# Joystick_final_rev02.net
KiCad netlist of a schematic drawn in EAGLE
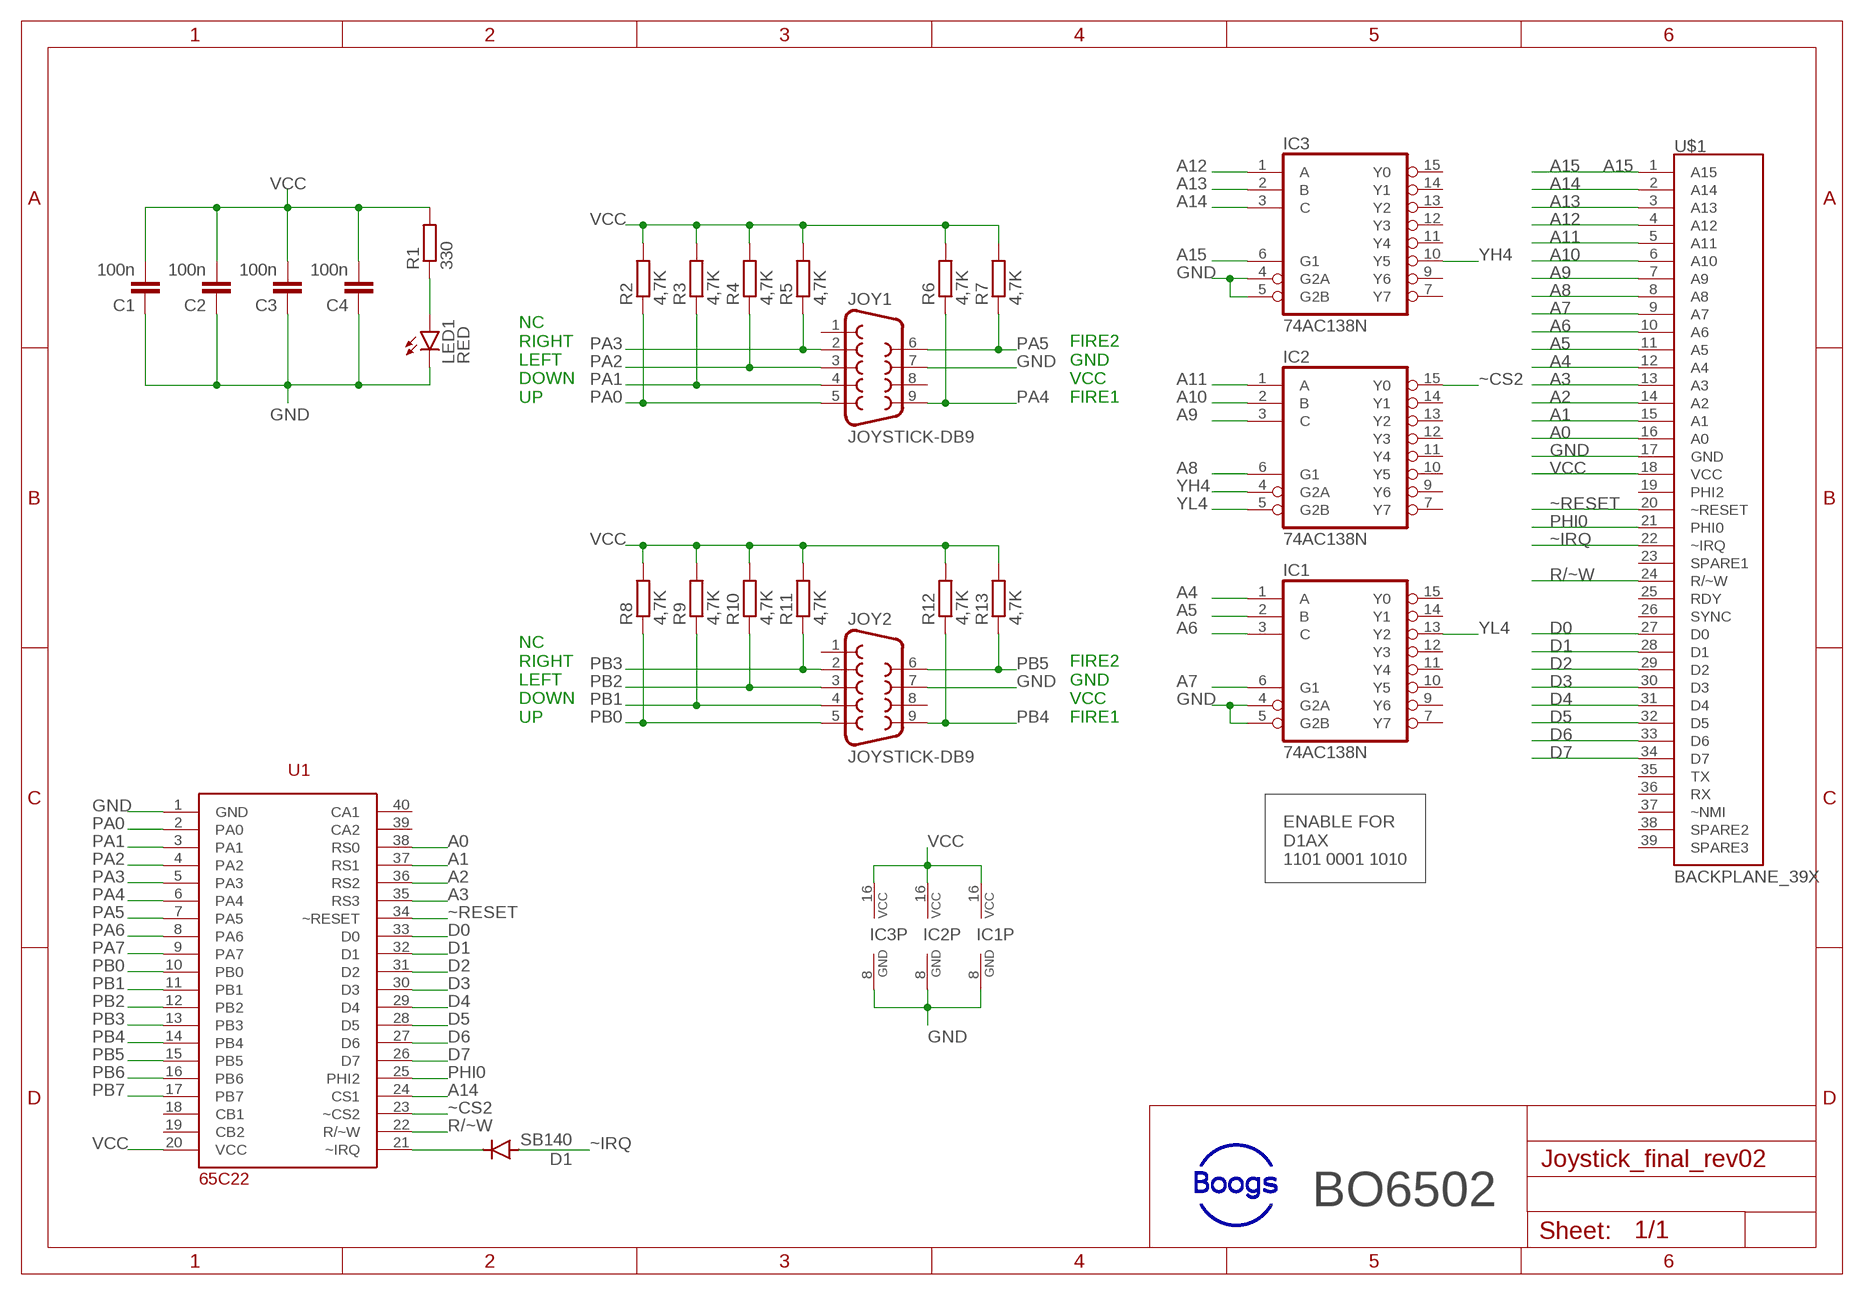
[diagram p0: schematic, sheet 1]

(export (version "E")
  (design (tool "Eeschema 10.0.6"))
  (components
    (comp (ref "C1")
      (value "100n")
      (footprint "eagle-import:C025-025X050")
      (libsource (lib "eagle-import") (part "C-EU025-025X050"))
    )
    (comp (ref "C2")
      (value "100n")
      (footprint "eagle-import:C025-025X050")
      (libsource (lib "eagle-import") (part "C-EU025-025X050"))
    )
    (comp (ref "C3")
      (value "100n")
      (footprint "eagle-import:C025-025X050")
      (libsource (lib "eagle-import") (part "C-EU025-025X050"))
    )
    (comp (ref "C4")
      (value "100n")
      (footprint "eagle-import:C025-025X050")
      (libsource (lib "eagle-import") (part "C-EU025-025X050"))
    )
    (comp (ref "D1")
      (value "SB140")
      (footprint "eagle-import:DO41-10")
      (libsource (lib "eagle-import") (part "1N4004"))
    )
    (comp (ref "IC1")
      (value "74AC138N")
      (footprint "eagle-import:DIL16")
      (libsource (lib "eagle-import") (part "74138NAC"))
    )
    (comp (ref "IC2")
      (value "74AC138N")
      (footprint "eagle-import:DIL16")
      (libsource (lib "eagle-import") (part "74138NAC"))
    )
    (comp (ref "IC3")
      (value "74AC138N")
      (footprint "eagle-import:DIL16")
      (libsource (lib "eagle-import") (part "74138NAC"))
    )
    (comp (ref "JOY1")
      (value "JOYSTICK-DB9")
      (footprint "eagle-import:F09HP")
      (libsource (lib "eagle-import") (part "F09HP"))
    )
    (comp (ref "JOY2")
      (value "JOYSTICK-DB9")
      (footprint "eagle-import:F09HP")
      (libsource (lib "eagle-import") (part "F09HP"))
    )
    (comp (ref "LED1")
      (value "RED")
      (footprint "eagle-import:LED5MM")
      (libsource (lib "eagle-import") (part "LED5MM"))
    )
    (comp (ref "R1")
      (value "330")
      (footprint "eagle-import:0207_10")
      (libsource (lib "eagle-import") (part "R-EU_0207/10"))
    )
    (comp (ref "R2")
      (value "4,7K")
      (footprint "eagle-import:0207_10")
      (libsource (lib "eagle-import") (part "R-EU_0207/10"))
    )
    (comp (ref "R3")
      (value "4,7K")
      (footprint "eagle-import:0207_10")
      (libsource (lib "eagle-import") (part "R-EU_0207/10"))
    )
    (comp (ref "R4")
      (value "4,7K")
      (footprint "eagle-import:0207_10")
      (libsource (lib "eagle-import") (part "R-EU_0207/10"))
    )
    (comp (ref "R5")
      (value "4,7K")
      (footprint "eagle-import:0207_10")
      (libsource (lib "eagle-import") (part "R-EU_0207/10"))
    )
    (comp (ref "R6")
      (value "4,7K")
      (footprint "eagle-import:0207_10")
      (libsource (lib "eagle-import") (part "R-EU_0207/10"))
    )
    (comp (ref "R7")
      (value "4,7K")
      (footprint "eagle-import:0207_10")
      (libsource (lib "eagle-import") (part "R-EU_0207/10"))
    )
    (comp (ref "R8")
      (value "4,7K")
      (footprint "eagle-import:0207_10")
      (libsource (lib "eagle-import") (part "R-EU_0207/10"))
    )
    (comp (ref "R9")
      (value "4,7K")
      (footprint "eagle-import:0207_10")
      (libsource (lib "eagle-import") (part "R-EU_0207/10"))
    )
    (comp (ref "R10")
      (value "4,7K")
      (footprint "eagle-import:0207_10")
      (libsource (lib "eagle-import") (part "R-EU_0207/10"))
    )
    (comp (ref "R11")
      (value "4,7K")
      (footprint "eagle-import:0207_10")
      (libsource (lib "eagle-import") (part "R-EU_0207/10"))
    )
    (comp (ref "R12")
      (value "4,7K")
      (footprint "eagle-import:0207_10")
      (libsource (lib "eagle-import") (part "R-EU_0207/10"))
    )
    (comp (ref "R13")
      (value "4,7K")
      (footprint "eagle-import:0207_10")
      (libsource (lib "eagle-import") (part "R-EU_0207/10"))
    )
    (comp (ref "U$1")
      (value "BACKPLANE_39X")
      (footprint "eagle-import:BP_39X")
      (fields (field (name "A15") "A15"))
      (libsource (lib "eagle-import") (part "BACKPLANE_39X"))
    )
    (comp (ref "U1")
      (value "65C22")
      (footprint "eagle-import:DIL40")
      (libsource (lib "eagle-import") (part "65C22"))
    )
  )
  (nets
    (net (code "1") (name "/A0") (class "Default")
      (node (ref "U$1") (pin "16") (pinfunction "A0_16") (pintype "bidirectional"))
      (node (ref "U1") (pin "38") (pinfunction "RS0_38") (pintype "bidirectional"))
    )
    (net (code "2") (name "/A1") (class "Default")
      (node (ref "U$1") (pin "15") (pinfunction "A1_15") (pintype "bidirectional"))
      (node (ref "U1") (pin "37") (pinfunction "RS1_37") (pintype "bidirectional"))
    )
    (net (code "3") (name "/A2") (class "Default")
      (node (ref "U$1") (pin "14") (pinfunction "A2_14") (pintype "bidirectional"))
      (node (ref "U1") (pin "36") (pinfunction "RS2_36") (pintype "bidirectional"))
    )
    (net (code "4") (name "/A3") (class "Default")
      (node (ref "U$1") (pin "13") (pinfunction "A3_13") (pintype "bidirectional"))
      (node (ref "U1") (pin "35") (pinfunction "RS3_35") (pintype "bidirectional"))
    )
    (net (code "5") (name "/A4") (class "Default")
      (node (ref "IC1") (pin "1") (pinfunction "A_1") (pintype "input"))
      (node (ref "U$1") (pin "12") (pinfunction "A4_12") (pintype "bidirectional"))
    )
    (net (code "6") (name "/A5") (class "Default")
      (node (ref "IC1") (pin "2") (pinfunction "B_2") (pintype "input"))
      (node (ref "U$1") (pin "11") (pinfunction "A5_11") (pintype "bidirectional"))
    )
    (net (code "7") (name "/A6") (class "Default")
      (node (ref "IC1") (pin "3") (pinfunction "C_3") (pintype "input"))
      (node (ref "U$1") (pin "10") (pinfunction "A6_10") (pintype "bidirectional"))
    )
    (net (code "8") (name "/A7") (class "Default")
      (node (ref "IC1") (pin "6") (pinfunction "G1_6") (pintype "input"))
      (node (ref "U$1") (pin "9") (pinfunction "A7_9") (pintype "bidirectional"))
    )
    (net (code "9") (name "/A8") (class "Default")
      (node (ref "IC2") (pin "6") (pinfunction "G1_6") (pintype "input"))
      (node (ref "U$1") (pin "8") (pinfunction "A8_8") (pintype "bidirectional"))
    )
    (net (code "10") (name "/A9") (class "Default")
      (node (ref "IC2") (pin "3") (pinfunction "C_3") (pintype "input"))
      (node (ref "U$1") (pin "7") (pinfunction "A9_7") (pintype "bidirectional"))
    )
    (net (code "11") (name "/A10") (class "Default")
      (node (ref "IC2") (pin "2") (pinfunction "B_2") (pintype "input"))
      (node (ref "U$1") (pin "6") (pinfunction "A10_6") (pintype "bidirectional"))
    )
    (net (code "12") (name "/A11") (class "Default")
      (node (ref "IC2") (pin "1") (pinfunction "A_1") (pintype "input"))
      (node (ref "U$1") (pin "5") (pinfunction "A11_5") (pintype "bidirectional"))
    )
    (net (code "13") (name "/A12") (class "Default")
      (node (ref "IC3") (pin "1") (pinfunction "A_1") (pintype "input"))
      (node (ref "U$1") (pin "4") (pinfunction "A12_4") (pintype "bidirectional"))
    )
    (net (code "14") (name "/A13") (class "Default")
      (node (ref "IC3") (pin "2") (pinfunction "B_2") (pintype "input"))
      (node (ref "U$1") (pin "3") (pinfunction "A13_3") (pintype "bidirectional"))
    )
    (net (code "15") (name "/A14") (class "Default")
      (node (ref "IC3") (pin "3") (pinfunction "C_3") (pintype "input"))
      (node (ref "U$1") (pin "2") (pinfunction "A14_2") (pintype "bidirectional"))
      (node (ref "U1") (pin "24") (pinfunction "CS1_24") (pintype "bidirectional"))
    )
    (net (code "16") (name "/A15") (class "Default")
      (node (ref "IC3") (pin "6") (pinfunction "G1_6") (pintype "input"))
      (node (ref "U$1") (pin "1") (pinfunction "A15_1") (pintype "bidirectional"))
    )
    (net (code "17") (name "/D0") (class "Default")
      (node (ref "U$1") (pin "27") (pinfunction "D0_27") (pintype "bidirectional"))
      (node (ref "U1") (pin "33") (pinfunction "D0_33") (pintype "bidirectional"))
    )
    (net (code "18") (name "/D1") (class "Default")
      (node (ref "U$1") (pin "28") (pinfunction "D1_28") (pintype "bidirectional"))
      (node (ref "U1") (pin "32") (pinfunction "D1_32") (pintype "bidirectional"))
    )
    (net (code "19") (name "/D2") (class "Default")
      (node (ref "U$1") (pin "29") (pinfunction "D2_29") (pintype "bidirectional"))
      (node (ref "U1") (pin "31") (pinfunction "D2_31") (pintype "bidirectional"))
    )
    (net (code "20") (name "/D3") (class "Default")
      (node (ref "U$1") (pin "30") (pinfunction "D3_30") (pintype "bidirectional"))
      (node (ref "U1") (pin "30") (pinfunction "D3_30") (pintype "bidirectional"))
    )
    (net (code "21") (name "/D4") (class "Default")
      (node (ref "U$1") (pin "31") (pinfunction "D4_31") (pintype "bidirectional"))
      (node (ref "U1") (pin "29") (pinfunction "D4_29") (pintype "bidirectional"))
    )
    (net (code "22") (name "/D5") (class "Default")
      (node (ref "U$1") (pin "32") (pinfunction "D5_32") (pintype "bidirectional"))
      (node (ref "U1") (pin "28") (pinfunction "D5_28") (pintype "bidirectional"))
    )
    (net (code "23") (name "/D6") (class "Default")
      (node (ref "U$1") (pin "33") (pinfunction "D6_33") (pintype "bidirectional"))
      (node (ref "U1") (pin "27") (pinfunction "D6_27") (pintype "bidirectional"))
    )
    (net (code "24") (name "/D7") (class "Default")
      (node (ref "U$1") (pin "34") (pinfunction "D7_34") (pintype "bidirectional"))
      (node (ref "U1") (pin "26") (pinfunction "D7_26") (pintype "bidirectional"))
    )
    (net (code "25") (name "/GND") (class "Default")
      (node (ref "C1") (pin "1") (pinfunction "1_1") (pintype "passive"))
      (node (ref "C2") (pin "1") (pinfunction "1_1") (pintype "passive"))
      (node (ref "C3") (pin "1") (pinfunction "1_1") (pintype "passive"))
      (node (ref "C4") (pin "1") (pinfunction "1_1") (pintype "passive"))
      (node (ref "IC1") (pin "4") (pinfunction "G2A_4") (pintype "input"))
      (node (ref "IC1") (pin "5") (pinfunction "G2B_5") (pintype "input"))
      (node (ref "IC1") (pin "8") (pinfunction "GND_8") (pintype "power_in"))
      (node (ref "IC2") (pin "8") (pinfunction "GND_8") (pintype "power_in"))
      (node (ref "IC3") (pin "4") (pinfunction "G2A_4") (pintype "input"))
      (node (ref "IC3") (pin "5") (pinfunction "G2B_5") (pintype "input"))
      (node (ref "IC3") (pin "8") (pinfunction "GND_8") (pintype "power_in"))
      (node (ref "JOY1") (pin "7") (pinfunction "7_7") (pintype "passive"))
      (node (ref "JOY2") (pin "7") (pinfunction "7_7") (pintype "passive"))
      (node (ref "LED1") (pin "K") (pinfunction "C_K") (pintype "passive"))
      (node (ref "U$1") (pin "17") (pinfunction "GND_17") (pintype "bidirectional"))
      (node (ref "U1") (pin "1") (pinfunction "GND_1") (pintype "bidirectional"))
    )
    (net (code "26") (name "/PA0") (class "Default")
      (node (ref "JOY1") (pin "5") (pinfunction "5_5") (pintype "passive"))
      (node (ref "R2") (pin "1") (pinfunction "1_1") (pintype "passive"))
      (node (ref "U1") (pin "2") (pinfunction "PA0_2") (pintype "bidirectional"))
    )
    (net (code "27") (name "/PA1") (class "Default")
      (node (ref "JOY1") (pin "4") (pinfunction "4_4") (pintype "passive"))
      (node (ref "R3") (pin "1") (pinfunction "1_1") (pintype "passive"))
      (node (ref "U1") (pin "3") (pinfunction "PA1_3") (pintype "bidirectional"))
    )
    (net (code "28") (name "/PA2") (class "Default")
      (node (ref "JOY1") (pin "3") (pinfunction "3_3") (pintype "passive"))
      (node (ref "R4") (pin "1") (pinfunction "1_1") (pintype "passive"))
      (node (ref "U1") (pin "4") (pinfunction "PA2_4") (pintype "bidirectional"))
    )
    (net (code "29") (name "/PA3") (class "Default")
      (node (ref "JOY1") (pin "2") (pinfunction "2_2") (pintype "passive"))
      (node (ref "R5") (pin "1") (pinfunction "1_1") (pintype "passive"))
      (node (ref "U1") (pin "5") (pinfunction "PA3_5") (pintype "bidirectional"))
    )
    (net (code "30") (name "/PA4") (class "Default")
      (node (ref "JOY1") (pin "9") (pinfunction "9_9") (pintype "passive"))
      (node (ref "R6") (pin "1") (pinfunction "1_1") (pintype "passive"))
      (node (ref "U1") (pin "6") (pinfunction "PA4_6") (pintype "bidirectional"))
    )
    (net (code "31") (name "/PA5") (class "Default")
      (node (ref "JOY1") (pin "6") (pinfunction "6_6") (pintype "passive"))
      (node (ref "R7") (pin "1") (pinfunction "1_1") (pintype "passive"))
      (node (ref "U1") (pin "7") (pinfunction "PA5_7") (pintype "bidirectional"))
    )
    (net (code "32") (name "/PA6") (class "Default")
      (node (ref "U1") (pin "8") (pinfunction "PA6_8") (pintype "bidirectional"))
    )
    (net (code "33") (name "/PA7") (class "Default")
      (node (ref "U1") (pin "9") (pinfunction "PA7_9") (pintype "bidirectional"))
    )
    (net (code "34") (name "/PB0") (class "Default")
      (node (ref "JOY2") (pin "5") (pinfunction "5_5") (pintype "passive"))
      (node (ref "R8") (pin "1") (pinfunction "1_1") (pintype "passive"))
      (node (ref "U1") (pin "10") (pinfunction "PB0_10") (pintype "bidirectional"))
    )
    (net (code "35") (name "/PB1") (class "Default")
      (node (ref "JOY2") (pin "4") (pinfunction "4_4") (pintype "passive"))
      (node (ref "R9") (pin "1") (pinfunction "1_1") (pintype "passive"))
      (node (ref "U1") (pin "11") (pinfunction "PB1_11") (pintype "bidirectional"))
    )
    (net (code "36") (name "/PB2") (class "Default")
      (node (ref "JOY2") (pin "3") (pinfunction "3_3") (pintype "passive"))
      (node (ref "R10") (pin "1") (pinfunction "1_1") (pintype "passive"))
      (node (ref "U1") (pin "12") (pinfunction "PB2_12") (pintype "bidirectional"))
    )
    (net (code "37") (name "/PB3") (class "Default")
      (node (ref "JOY2") (pin "2") (pinfunction "2_2") (pintype "passive"))
      (node (ref "R11") (pin "1") (pinfunction "1_1") (pintype "passive"))
      (node (ref "U1") (pin "13") (pinfunction "PB3_13") (pintype "bidirectional"))
    )
    (net (code "38") (name "/PB4") (class "Default")
      (node (ref "JOY2") (pin "9") (pinfunction "9_9") (pintype "passive"))
      (node (ref "R12") (pin "1") (pinfunction "1_1") (pintype "passive"))
      (node (ref "U1") (pin "14") (pinfunction "PB4_14") (pintype "bidirectional"))
    )
    (net (code "39") (name "/PB5") (class "Default")
      (node (ref "JOY2") (pin "6") (pinfunction "6_6") (pintype "passive"))
      (node (ref "R13") (pin "1") (pinfunction "1_1") (pintype "passive"))
      (node (ref "U1") (pin "15") (pinfunction "PB5_15") (pintype "bidirectional"))
    )
    (net (code "40") (name "/PB6") (class "Default")
      (node (ref "U1") (pin "16") (pinfunction "PB6_16") (pintype "bidirectional"))
    )
    (net (code "41") (name "/PB7") (class "Default")
      (node (ref "U1") (pin "17") (pinfunction "PB7_17") (pintype "bidirectional"))
    )
    (net (code "42") (name "/PHI0") (class "Default")
      (node (ref "U$1") (pin "21") (pinfunction "PHI0_21") (pintype "bidirectional"))
      (node (ref "U1") (pin "25") (pinfunction "PHI2_25") (pintype "bidirectional"))
    )
    (net (code "43") (name "/R{slash}~{W}") (class "Default")
      (node (ref "U$1") (pin "24") (pinfunction "R/~{W}_24") (pintype "bidirectional"))
      (node (ref "U1") (pin "22") (pinfunction "R/~{W}_22") (pintype "bidirectional"))
    )
    (net (code "44") (name "/VCC") (class "Default")
      (node (ref "C1") (pin "2") (pinfunction "2_2") (pintype "passive"))
      (node (ref "C2") (pin "2") (pinfunction "2_2") (pintype "passive"))
      (node (ref "C3") (pin "2") (pinfunction "2_2") (pintype "passive"))
      (node (ref "C4") (pin "2") (pinfunction "2_2") (pintype "passive"))
      (node (ref "IC1") (pin "16") (pinfunction "VCC_16") (pintype "power_in"))
      (node (ref "IC2") (pin "16") (pinfunction "VCC_16") (pintype "power_in"))
      (node (ref "IC3") (pin "16") (pinfunction "VCC_16") (pintype "power_in"))
      (node (ref "R1") (pin "2") (pinfunction "2_2") (pintype "passive"))
      (node (ref "R10") (pin "2") (pinfunction "2_2") (pintype "passive"))
      (node (ref "R11") (pin "2") (pinfunction "2_2") (pintype "passive"))
      (node (ref "R12") (pin "2") (pinfunction "2_2") (pintype "passive"))
      (node (ref "R13") (pin "2") (pinfunction "2_2") (pintype "passive"))
      (node (ref "R2") (pin "2") (pinfunction "2_2") (pintype "passive"))
      (node (ref "R3") (pin "2") (pinfunction "2_2") (pintype "passive"))
      (node (ref "R4") (pin "2") (pinfunction "2_2") (pintype "passive"))
      (node (ref "R5") (pin "2") (pinfunction "2_2") (pintype "passive"))
      (node (ref "R6") (pin "2") (pinfunction "2_2") (pintype "passive"))
      (node (ref "R7") (pin "2") (pinfunction "2_2") (pintype "passive"))
      (node (ref "R8") (pin "2") (pinfunction "2_2") (pintype "passive"))
      (node (ref "R9") (pin "2") (pinfunction "2_2") (pintype "passive"))
      (node (ref "U$1") (pin "18") (pinfunction "VCC_18") (pintype "bidirectional"))
      (node (ref "U1") (pin "20") (pinfunction "VCC_20") (pintype "bidirectional"))
    )
    (net (code "45") (name "/YH4") (class "Default")
      (node (ref "IC2") (pin "4") (pinfunction "G2A_4") (pintype "input"))
      (node (ref "IC3") (pin "10") (pinfunction "Y5_10") (pintype "output"))
    )
    (net (code "46") (name "/YL4") (class "Default")
      (node (ref "IC1") (pin "13") (pinfunction "Y2_13") (pintype "output"))
      (node (ref "IC2") (pin "5") (pinfunction "G2B_5") (pintype "input"))
    )
    (net (code "47") (name "/~{CS2}") (class "Default")
      (node (ref "IC2") (pin "15") (pinfunction "Y0_15") (pintype "output"))
      (node (ref "U1") (pin "23") (pinfunction "~{CS2}_23") (pintype "bidirectional"))
    )
    (net (code "48") (name "/~{IRQ}") (class "Default")
      (node (ref "D1") (pin "A") (pinfunction "A_A") (pintype "passive"))
      (node (ref "U$1") (pin "22") (pinfunction "~{IRQ}_22") (pintype "bidirectional"))
    )
    (net (code "49") (name "/~{RESET}") (class "Default")
      (node (ref "U$1") (pin "20") (pinfunction "~{RESET}_20") (pintype "bidirectional"))
      (node (ref "U1") (pin "34") (pinfunction "~{RESET}_34") (pintype "bidirectional"))
    )
    (net (code "50") (name "Net-(LED1-PadA)") (class "Default")
      (node (ref "LED1") (pin "A") (pinfunction "A_A") (pintype "passive"))
      (node (ref "R1") (pin "1") (pinfunction "1_1") (pintype "passive"))
    )
    (net (code "51") (name "Net-(U1-~{IRQ})") (class "Default")
      (node (ref "D1") (pin "C") (pinfunction "C_C") (pintype "passive"))
      (node (ref "U1") (pin "21") (pinfunction "~{IRQ}_21") (pintype "bidirectional"))
    )
    (net (code "52") (name "unconnected-(IC1A-Y0-Pad15)") (class "Default")
      (node (ref "IC1") (pin "15") (pinfunction "Y0_15") (pintype "output"))
    )
    (net (code "53") (name "unconnected-(IC1A-Y1-Pad14)") (class "Default")
      (node (ref "IC1") (pin "14") (pinfunction "Y1_14") (pintype "output"))
    )
    (net (code "54") (name "unconnected-(IC1A-Y3-Pad12)") (class "Default")
      (node (ref "IC1") (pin "12") (pinfunction "Y3_12") (pintype "output"))
    )
    (net (code "55") (name "unconnected-(IC1A-Y4-Pad11)") (class "Default")
      (node (ref "IC1") (pin "11") (pinfunction "Y4_11") (pintype "output"))
    )
    (net (code "56") (name "unconnected-(IC1A-Y5-Pad10)") (class "Default")
      (node (ref "IC1") (pin "10") (pinfunction "Y5_10") (pintype "output"))
    )
    (net (code "57") (name "unconnected-(IC1A-Y6-Pad9)") (class "Default")
      (node (ref "IC1") (pin "9") (pinfunction "Y6_9") (pintype "output"))
    )
    (net (code "58") (name "unconnected-(IC1A-Y7-Pad7)") (class "Default")
      (node (ref "IC1") (pin "7") (pinfunction "Y7_7") (pintype "output"))
    )
    (net (code "59") (name "unconnected-(IC2A-Y1-Pad14)") (class "Default")
      (node (ref "IC2") (pin "14") (pinfunction "Y1_14") (pintype "output"))
    )
    (net (code "60") (name "unconnected-(IC2A-Y2-Pad13)") (class "Default")
      (node (ref "IC2") (pin "13") (pinfunction "Y2_13") (pintype "output"))
    )
    (net (code "61") (name "unconnected-(IC2A-Y3-Pad12)") (class "Default")
      (node (ref "IC2") (pin "12") (pinfunction "Y3_12") (pintype "output"))
    )
    (net (code "62") (name "unconnected-(IC2A-Y4-Pad11)") (class "Default")
      (node (ref "IC2") (pin "11") (pinfunction "Y4_11") (pintype "output"))
    )
    (net (code "63") (name "unconnected-(IC2A-Y5-Pad10)") (class "Default")
      (node (ref "IC2") (pin "10") (pinfunction "Y5_10") (pintype "output"))
    )
    (net (code "64") (name "unconnected-(IC2A-Y6-Pad9)") (class "Default")
      (node (ref "IC2") (pin "9") (pinfunction "Y6_9") (pintype "output"))
    )
    (net (code "65") (name "unconnected-(IC2A-Y7-Pad7)") (class "Default")
      (node (ref "IC2") (pin "7") (pinfunction "Y7_7") (pintype "output"))
    )
    (net (code "66") (name "unconnected-(IC3A-Y0-Pad15)") (class "Default")
      (node (ref "IC3") (pin "15") (pinfunction "Y0_15") (pintype "output"))
    )
    (net (code "67") (name "unconnected-(IC3A-Y1-Pad14)") (class "Default")
      (node (ref "IC3") (pin "14") (pinfunction "Y1_14") (pintype "output"))
    )
    (net (code "68") (name "unconnected-(IC3A-Y2-Pad13)") (class "Default")
      (node (ref "IC3") (pin "13") (pinfunction "Y2_13") (pintype "output"))
    )
    (net (code "69") (name "unconnected-(IC3A-Y3-Pad12)") (class "Default")
      (node (ref "IC3") (pin "12") (pinfunction "Y3_12") (pintype "output"))
    )
    (net (code "70") (name "unconnected-(IC3A-Y4-Pad11)") (class "Default")
      (node (ref "IC3") (pin "11") (pinfunction "Y4_11") (pintype "output"))
    )
    (net (code "71") (name "unconnected-(IC3A-Y6-Pad9)") (class "Default")
      (node (ref "IC3") (pin "9") (pinfunction "Y6_9") (pintype "output"))
    )
    (net (code "72") (name "unconnected-(IC3A-Y7-Pad7)") (class "Default")
      (node (ref "IC3") (pin "7") (pinfunction "Y7_7") (pintype "output"))
    )
    (net (code "73") (name "unconnected-(JOY1-Pad1)") (class "Default")
      (node (ref "JOY1") (pin "1") (pinfunction "1_1") (pintype "passive"))
    )
    (net (code "74") (name "unconnected-(JOY1-Pad8)") (class "Default")
      (node (ref "JOY1") (pin "8") (pinfunction "8_8") (pintype "passive"))
    )
    (net (code "75") (name "unconnected-(JOY2-Pad1)") (class "Default")
      (node (ref "JOY2") (pin "1") (pinfunction "1_1") (pintype "passive"))
    )
    (net (code "76") (name "unconnected-(JOY2-Pad8)") (class "Default")
      (node (ref "JOY2") (pin "8") (pinfunction "8_8") (pintype "passive"))
    )
    (net (code "77") (name "unconnected-(U$1-PHI2-Pad19)") (class "Default")
      (node (ref "U$1") (pin "19") (pinfunction "PHI2_19") (pintype "bidirectional"))
    )
    (net (code "78") (name "unconnected-(U$1-RDY-Pad25)") (class "Default")
      (node (ref "U$1") (pin "25") (pinfunction "RDY_25") (pintype "bidirectional"))
    )
    (net (code "79") (name "unconnected-(U$1-RX-Pad36)") (class "Default")
      (node (ref "U$1") (pin "36") (pinfunction "RX_36") (pintype "bidirectional"))
    )
    (net (code "80") (name "unconnected-(U$1-SPARE1-Pad23)") (class "Default")
      (node (ref "U$1") (pin "23") (pinfunction "SPARE1_23") (pintype "bidirectional"))
    )
    (net (code "81") (name "unconnected-(U$1-SPARE2-Pad38)") (class "Default")
      (node (ref "U$1") (pin "38") (pinfunction "SPARE2_38") (pintype "bidirectional"))
    )
    (net (code "82") (name "unconnected-(U$1-SPARE3-Pad39)") (class "Default")
      (node (ref "U$1") (pin "39") (pinfunction "SPARE3_39") (pintype "bidirectional"))
    )
    (net (code "83") (name "unconnected-(U$1-SYNC-Pad26)") (class "Default")
      (node (ref "U$1") (pin "26") (pinfunction "SYNC_26") (pintype "bidirectional"))
    )
    (net (code "84") (name "unconnected-(U$1-TX-Pad35)") (class "Default")
      (node (ref "U$1") (pin "35") (pinfunction "TX_35") (pintype "bidirectional"))
    )
    (net (code "85") (name "unconnected-(U$1-~{NMI}-Pad37)") (class "Default")
      (node (ref "U$1") (pin "37") (pinfunction "~{NMI}_37") (pintype "bidirectional"))
    )
    (net (code "86") (name "unconnected-(U1-CA1-Pad40)") (class "Default")
      (node (ref "U1") (pin "40") (pinfunction "CA1_40") (pintype "bidirectional"))
    )
    (net (code "87") (name "unconnected-(U1-CA2-Pad39)") (class "Default")
      (node (ref "U1") (pin "39") (pinfunction "CA2_39") (pintype "bidirectional"))
    )
    (net (code "88") (name "unconnected-(U1-CB1-Pad18)") (class "Default")
      (node (ref "U1") (pin "18") (pinfunction "CB1_18") (pintype "bidirectional"))
    )
    (net (code "89") (name "unconnected-(U1-CB2-Pad19)") (class "Default")
      (node (ref "U1") (pin "19") (pinfunction "CB2_19") (pintype "bidirectional"))
    )
  )
)
